# 09-_-.net
KiCad netlist of a schematic drawn in Altium Designer
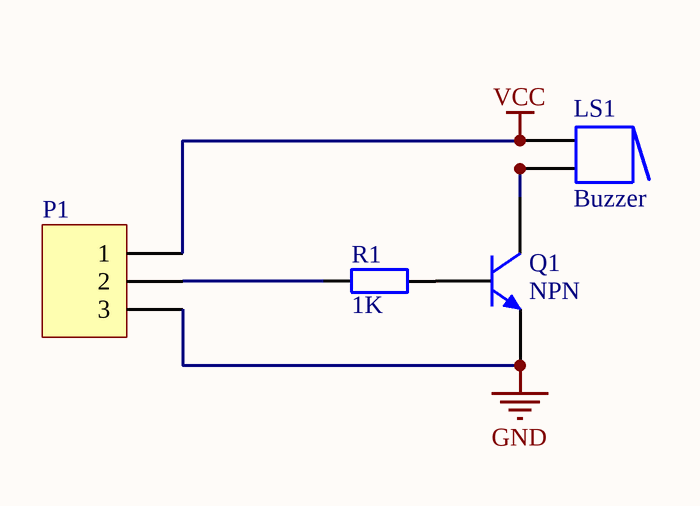
[diagram p0: 09-蜂鸣器模块-原理图.SchDoc]

(export (version "E")
  (design (tool "Eeschema 10.0.6"))
  (components
    (comp (ref "LS1")
      (value "Buzzer")
      (footprint "ABSM-1574")
      (description "Magnetic Transducer Buzzer")
      (fields (field (name "PUBLISHER") "Altium Limited"))
      (libsource (lib "Miscellaneous Devices") (part "Buzzer"))
    )
    (comp (ref "P1")
      (value "Header 3")
      (footprint "HDR1X3")
      (description "Header, 3-Pin")
      (fields (field (name "PUBLISHER") "Altium Limited"))
      (libsource (lib "Miscellaneous Connectors") (part "Header 3"))
    )
    (comp (ref "Q1")
      (value "NPN")
      (footprint "sot-23")
      (description "NPN General Purpose Amplifier")
      (fields (field (name "PUBLISHER") "Altium Limited"))
      (libsource (lib "Miscellaneous Devices") (part "2N3904"))
    )
    (comp (ref "R1")
      (value "1K")
      (footprint "r0603")
      (description "Resistor")
      (fields (field (name "Comment") "Res2") (field (name "PUBLISHER") "Altium Limited"))
      (libsource (lib "Miscellaneous Devices") (part "Res2"))
    )
  )
  (nets
    (net (code "1") (name "GND") (class "Default")
      (node (ref "P1") (pin "3") (pinfunction "3_3") (pintype "passive"))
      (node (ref "Q1") (pin "2") (pinfunction "E_2") (pintype "passive"))
    )
    (net (code "2") (name "Net-(P1-Pad2)") (class "Default")
      (node (ref "P1") (pin "2") (pinfunction "2_2") (pintype "passive"))
      (node (ref "R1") (pin "1") (pinfunction "1_1") (pintype "passive"))
    )
    (net (code "3") (name "Net-(Q1-B)") (class "Default")
      (node (ref "Q1") (pin "1") (pinfunction "B_1") (pintype "passive"))
      (node (ref "R1") (pin "2") (pinfunction "2_2") (pintype "passive"))
    )
    (net (code "4") (name "Net-(Q1-C)") (class "Default")
      (node (ref "LS1") (pin "2") (pinfunction "2_2") (pintype "passive"))
      (node (ref "LS1") (pin "2A") (pinfunction "2A_2A") (pintype "passive"))
      (node (ref "Q1") (pin "3") (pinfunction "C_3") (pintype "passive"))
    )
    (net (code "5") (name "VCC") (class "Default")
      (node (ref "LS1") (pin "1") (pinfunction "1_1") (pintype "passive"))
      (node (ref "LS1") (pin "1A") (pinfunction "1A_1A") (pintype "passive"))
      (node (ref "P1") (pin "1") (pinfunction "1_1") (pintype "passive"))
    )
  )
)
